# Buffer.net
KiCad netlist of a schematic drawn in Altium Designer
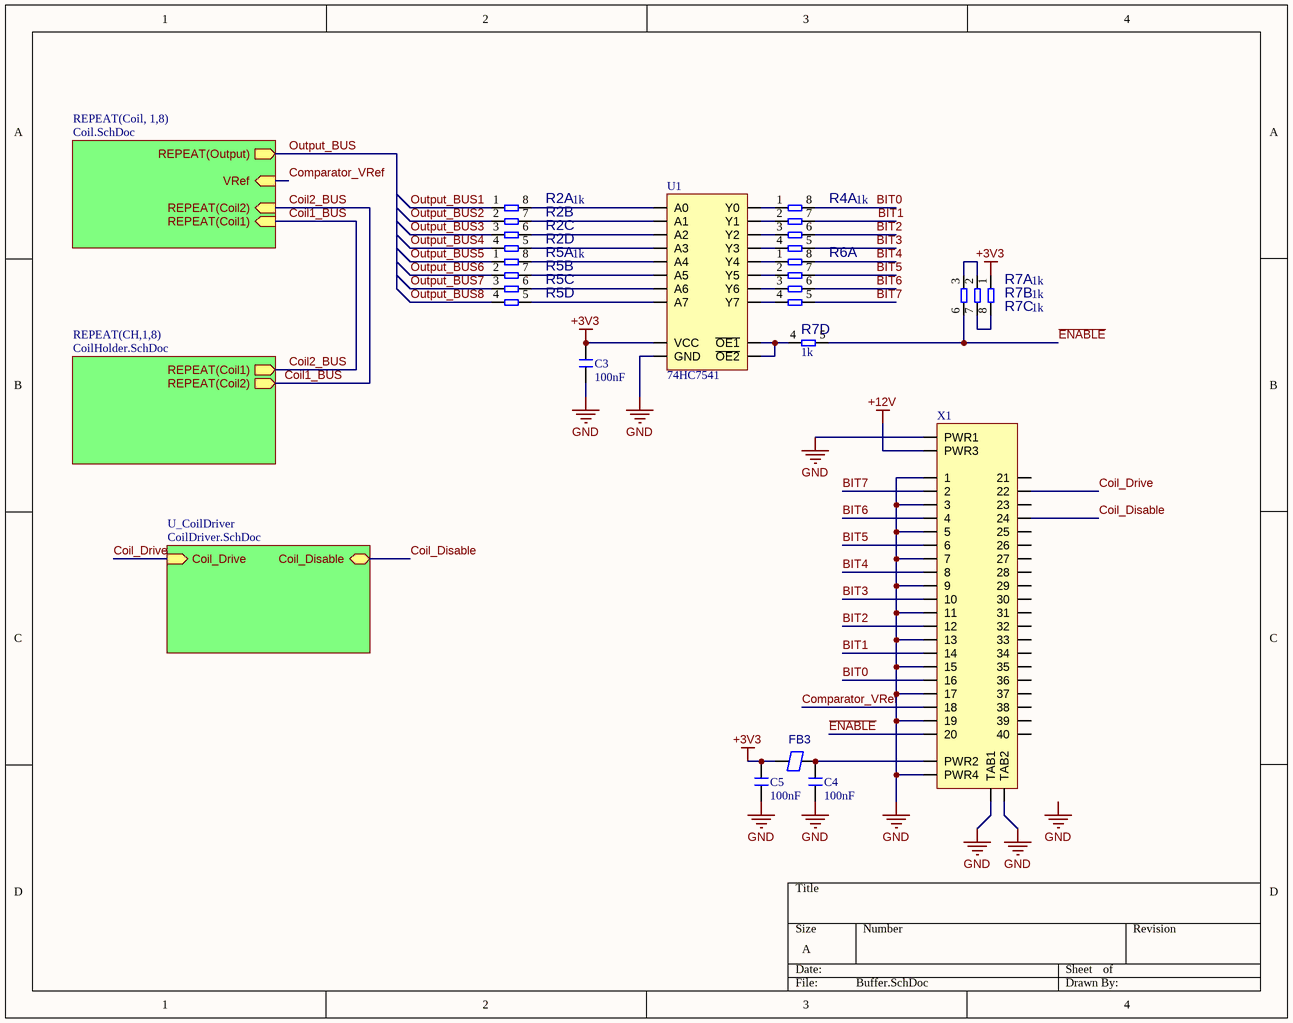
[diagram p0: Buffer.SchDoc]

(export (version "E")
  (design (tool "Eeschema 10.0.6"))
  (components
    (comp (ref "C3")
      (value "100nF")
      (footprint "C0603_N")
      (description "Capacitor MLCC")
      (fields
        (field (name "MANUFACTURER") "Yageo")
        (field (name "MANUFACTURER PART NUMBER") "CC0603KRX7R9BB104")
      )
      (libsource (lib "wes") (part "Capacitor"))
    )
    (comp (ref "C4")
      (value "100nF")
      (footprint "C0603_N")
      (description "Capacitor MLCC")
      (fields
        (field (name "MANUFACTURER") "Yageo")
        (field (name "MANUFACTURER PART NUMBER") "CC0603KRX7R9BB104")
      )
      (libsource (lib "wes") (part "Capacitor"))
    )
    (comp (ref "C5")
      (value "100nF")
      (footprint "C0603_N")
      (description "Capacitor MLCC")
      (fields
        (field (name "MANUFACTURER") "Yageo")
        (field (name "MANUFACTURER PART NUMBER") "CC0603KRX7R9BB104")
      )
      (libsource (lib "wes") (part "Capacitor"))
    )
    (comp (ref "FB3")
      (value "Ferrite Bead")
      (footprint "F0603_N")
      (libsource (lib "wes") (part "Ferrite Bead"))
    )
    (comp (ref "R2")
      (value "Resistor Array - 4P")
      (footprint "YC164")
      (fields (field (name "Comment") "Resistor Array - 4P"))
      (libsource (lib "wes") (part "Resistor Array - 4P"))
    )
    (comp (ref "R4")
      (value "1k")
      (footprint "YC164")
      (fields (field (name "Comment") "Resistor Array - 4P"))
      (libsource (lib "wes") (part "Resistor Array - 4P"))
    )
    (comp (ref "R5")
      (value "Resistor Array - 4P")
      (footprint "YC164")
      (libsource (lib "wes") (part "Resistor Array - 4P"))
    )
    (comp (ref "R6")
      (value "Resistor Array - 4P")
      (footprint "YC164")
      (libsource (lib "wes") (part "Resistor Array - 4P"))
    )
    (comp (ref "R7")
      (value "1k")
      (footprint "YC164")
      (fields (field (name "Comment") "Resistor Array - 4P"))
      (libsource (lib "wes") (part "Resistor Array - 4P"))
    )
    (comp (ref "U1")
      (value "74HC7541")
      (footprint "TSSOP20_N")
      (description "Schmitt Trigger Octal")
      (libsource (lib "wes") (part "74HC7541"))
    )
    (comp (ref "X1")
      (value "FX23 Right Angle Receptacle")
      (footprint "FX23-40S-0.5SH")
      (description "FX23 Right Angle Receptacle 40 Pos")
      (libsource (lib "wes") (part "FX23-40S-0.5SH"))
    )
  )
  (nets
    (net (code "1") (name "+3V3") (class "Default")
      (node (ref "C3") (pin "1") (pintype "passive"))
      (node (ref "C5") (pin "1") (pintype "passive"))
      (node (ref "FB3") (pin "2") (pinfunction "2_2") (pintype "passive"))
      (node (ref "R7") (pin "1") (pinfunction "1_1") (pintype "passive"))
      (node (ref "U1") (pin "20") (pinfunction "VCC_20") (pintype "passive"))
    )
    (net (code "2") (name "+12V") (class "Default")
      (node (ref "X1") (pin "PWR3") (pinfunction "PWR3_PWR3") (pintype "power_in"))
    )
    (net (code "3") (name "/BIT0") (class "Default")
      (node (ref "R4") (pin "8") (pinfunction "8_8") (pintype "passive"))
      (node (ref "X1") (pin "16") (pinfunction "16_16") (pintype "power_in"))
    )
    (net (code "4") (name "/BIT1") (class "Default")
      (node (ref "R4") (pin "7") (pinfunction "7_7") (pintype "passive"))
      (node (ref "X1") (pin "14") (pinfunction "14_14") (pintype "power_in"))
    )
    (net (code "5") (name "/BIT2") (class "Default")
      (node (ref "R4") (pin "6") (pinfunction "6_6") (pintype "passive"))
      (node (ref "X1") (pin "12") (pinfunction "12_12") (pintype "power_in"))
    )
    (net (code "6") (name "/BIT3") (class "Default")
      (node (ref "R4") (pin "5") (pinfunction "5_5") (pintype "passive"))
      (node (ref "X1") (pin "10") (pinfunction "10_10") (pintype "power_in"))
    )
    (net (code "7") (name "/BIT4") (class "Default")
      (node (ref "R6") (pin "8") (pinfunction "8_8") (pintype "passive"))
      (node (ref "X1") (pin "8") (pinfunction "8_8") (pintype "power_in"))
    )
    (net (code "8") (name "/BIT5") (class "Default")
      (node (ref "R6") (pin "7") (pinfunction "7_7") (pintype "passive"))
      (node (ref "X1") (pin "6") (pinfunction "6_6") (pintype "power_in"))
    )
    (net (code "9") (name "/BIT6") (class "Default")
      (node (ref "R6") (pin "6") (pinfunction "6_6") (pintype "passive"))
      (node (ref "X1") (pin "4") (pinfunction "4_4") (pintype "power_in"))
    )
    (net (code "10") (name "/BIT7") (class "Default")
      (node (ref "R6") (pin "5") (pinfunction "5_5") (pintype "passive"))
      (node (ref "X1") (pin "2") (pinfunction "2_2") (pintype "power_in"))
    )
    (net (code "13") (name "/Coil_Disable") (class "Default")
      (node (ref "X1") (pin "24") (pinfunction "24_24") (pintype "power_in"))
    )
    (net (code "14") (name "/Coil_Drive") (class "Default")
      (node (ref "X1") (pin "22") (pinfunction "22_22") (pintype "power_in"))
    )
    (net (code "15") (name "/Comparator_VRef") (class "Default")
      (node (ref "X1") (pin "18") (pinfunction "18_18") (pintype "power_in"))
    )
    (net (code "17") (name "/Output_BUS1") (class "Default")
      (node (ref "R2") (pin "1") (pinfunction "1_1") (pintype "passive"))
    )
    (net (code "18") (name "/Output_BUS2") (class "Default")
      (node (ref "R2") (pin "2") (pinfunction "2_2") (pintype "passive"))
    )
    (net (code "19") (name "/Output_BUS3") (class "Default")
      (node (ref "R2") (pin "3") (pinfunction "3_3") (pintype "passive"))
    )
    (net (code "20") (name "/Output_BUS4") (class "Default")
      (node (ref "R2") (pin "4") (pinfunction "4_4") (pintype "passive"))
    )
    (net (code "21") (name "/Output_BUS5") (class "Default")
      (node (ref "R5") (pin "1") (pinfunction "1_1") (pintype "passive"))
    )
    (net (code "22") (name "/Output_BUS6") (class "Default")
      (node (ref "R5") (pin "2") (pinfunction "2_2") (pintype "passive"))
    )
    (net (code "23") (name "/Output_BUS7") (class "Default")
      (node (ref "R5") (pin "3") (pinfunction "3_3") (pintype "passive"))
    )
    (net (code "24") (name "/Output_BUS8") (class "Default")
      (node (ref "R5") (pin "4") (pinfunction "4_4") (pintype "passive"))
    )
    (net (code "25") (name "/~{ENABLE}") (class "Default")
      (node (ref "R7") (pin "5") (pinfunction "5_5") (pintype "passive"))
      (node (ref "R7") (pin "6") (pinfunction "6_6") (pintype "passive"))
      (node (ref "X1") (pin "20") (pinfunction "20_20") (pintype "power_in"))
    )
    (net (code "26") (name "GND") (class "Default")
      (node (ref "C3") (pin "2") (pintype "passive"))
      (node (ref "C4") (pin "2") (pintype "passive"))
      (node (ref "C5") (pin "2") (pintype "passive"))
      (node (ref "U1") (pin "10") (pinfunction "GND_10") (pintype "passive"))
      (node (ref "X1") (pin "1") (pinfunction "1_1") (pintype "power_in"))
      (node (ref "X1") (pin "11") (pinfunction "11_11") (pintype "power_in"))
      (node (ref "X1") (pin "13") (pinfunction "13_13") (pintype "power_in"))
      (node (ref "X1") (pin "15") (pinfunction "15_15") (pintype "power_in"))
      (node (ref "X1") (pin "17") (pinfunction "17_17") (pintype "power_in"))
      (node (ref "X1") (pin "19") (pinfunction "19_19") (pintype "power_in"))
      (node (ref "X1") (pin "3") (pinfunction "3_3") (pintype "power_in"))
      (node (ref "X1") (pin "5") (pinfunction "5_5") (pintype "power_in"))
      (node (ref "X1") (pin "7") (pinfunction "7_7") (pintype "power_in"))
      (node (ref "X1") (pin "9") (pinfunction "9_9") (pintype "power_in"))
      (node (ref "X1") (pin "PWR1") (pinfunction "PWR1_PWR1") (pintype "power_in"))
      (node (ref "X1") (pin "PWR4") (pinfunction "PWR4_PWR4") (pintype "power_in"))
      (node (ref "X1") (pin "TAB1") (pinfunction "TAB1_TAB1") (pintype "power_in"))
      (node (ref "X1") (pin "TAB2") (pinfunction "TAB2_TAB2") (pintype "power_in"))
    )
    (net (code "27") (name "Net-(C4-Pad1)") (class "Default")
      (node (ref "C4") (pin "1") (pintype "passive"))
      (node (ref "FB3") (pin "1") (pinfunction "1_1") (pintype "passive"))
      (node (ref "X1") (pin "PWR2") (pinfunction "PWR2_PWR2") (pintype "power_in"))
    )
    (net (code "28") (name "Net-(R7-Pad2)") (class "Default")
      (node (ref "R7") (pin "2") (pinfunction "2_2") (pintype "passive"))
      (node (ref "R7") (pin "3") (pinfunction "3_3") (pintype "passive"))
    )
    (net (code "29") (name "Net-(R7-Pad7)") (class "Default")
      (node (ref "R7") (pin "7") (pinfunction "7_7") (pintype "passive"))
      (node (ref "R7") (pin "8") (pinfunction "8_8") (pintype "passive"))
    )
    (net (code "30") (name "Net-(U1-A0)") (class "Default")
      (node (ref "R2") (pin "8") (pinfunction "8_8") (pintype "passive"))
      (node (ref "U1") (pin "2") (pinfunction "A0_2") (pintype "passive"))
    )
    (net (code "31") (name "Net-(U1-A1)") (class "Default")
      (node (ref "R2") (pin "7") (pinfunction "7_7") (pintype "passive"))
      (node (ref "U1") (pin "3") (pinfunction "A1_3") (pintype "passive"))
    )
    (net (code "32") (name "Net-(U1-A2)") (class "Default")
      (node (ref "R2") (pin "6") (pinfunction "6_6") (pintype "passive"))
      (node (ref "U1") (pin "4") (pinfunction "A2_4") (pintype "passive"))
    )
    (net (code "33") (name "Net-(U1-A3)") (class "Default")
      (node (ref "R2") (pin "5") (pinfunction "5_5") (pintype "passive"))
      (node (ref "U1") (pin "5") (pinfunction "A3_5") (pintype "passive"))
    )
    (net (code "34") (name "Net-(U1-A4)") (class "Default")
      (node (ref "R5") (pin "8") (pinfunction "8_8") (pintype "passive"))
      (node (ref "U1") (pin "6") (pinfunction "A4_6") (pintype "passive"))
    )
    (net (code "35") (name "Net-(U1-A5)") (class "Default")
      (node (ref "R5") (pin "7") (pinfunction "7_7") (pintype "passive"))
      (node (ref "U1") (pin "7") (pinfunction "A5_7") (pintype "passive"))
    )
    (net (code "36") (name "Net-(U1-A6)") (class "Default")
      (node (ref "R5") (pin "6") (pinfunction "6_6") (pintype "passive"))
      (node (ref "U1") (pin "8") (pinfunction "A6_8") (pintype "passive"))
    )
    (net (code "37") (name "Net-(U1-A7)") (class "Default")
      (node (ref "R5") (pin "5") (pinfunction "5_5") (pintype "passive"))
      (node (ref "U1") (pin "9") (pinfunction "A7_9") (pintype "passive"))
    )
    (net (code "38") (name "Net-(U1-Y0)") (class "Default")
      (node (ref "R4") (pin "1") (pinfunction "1_1") (pintype "passive"))
      (node (ref "U1") (pin "18") (pinfunction "Y0_18") (pintype "passive"))
    )
    (net (code "39") (name "Net-(U1-Y1)") (class "Default")
      (node (ref "R4") (pin "2") (pinfunction "2_2") (pintype "passive"))
      (node (ref "U1") (pin "17") (pinfunction "Y1_17") (pintype "passive"))
    )
    (net (code "40") (name "Net-(U1-Y2)") (class "Default")
      (node (ref "R4") (pin "3") (pinfunction "3_3") (pintype "passive"))
      (node (ref "U1") (pin "16") (pinfunction "Y2_16") (pintype "passive"))
    )
    (net (code "41") (name "Net-(U1-Y3)") (class "Default")
      (node (ref "R4") (pin "4") (pinfunction "4_4") (pintype "passive"))
      (node (ref "U1") (pin "15") (pinfunction "Y3_15") (pintype "passive"))
    )
    (net (code "42") (name "Net-(U1-Y4)") (class "Default")
      (node (ref "R6") (pin "1") (pinfunction "1_1") (pintype "passive"))
      (node (ref "U1") (pin "14") (pinfunction "Y4_14") (pintype "passive"))
    )
    (net (code "43") (name "Net-(U1-Y5)") (class "Default")
      (node (ref "R6") (pin "2") (pinfunction "2_2") (pintype "passive"))
      (node (ref "U1") (pin "13") (pinfunction "Y5_13") (pintype "passive"))
    )
    (net (code "44") (name "Net-(U1-Y6)") (class "Default")
      (node (ref "R6") (pin "3") (pinfunction "3_3") (pintype "passive"))
      (node (ref "U1") (pin "12") (pinfunction "Y6_12") (pintype "passive"))
    )
    (net (code "45") (name "Net-(U1-Y7)") (class "Default")
      (node (ref "R6") (pin "4") (pinfunction "4_4") (pintype "passive"))
      (node (ref "U1") (pin "11") (pinfunction "Y7_11") (pintype "passive"))
    )
    (net (code "46") (name "Net-(U1-~{OE1})") (class "Default")
      (node (ref "R7") (pin "4") (pinfunction "4_4") (pintype "passive"))
      (node (ref "U1") (pin "1") (pinfunction "~{OE1}_1") (pintype "passive"))
      (node (ref "U1") (pin "19") (pinfunction "~{OE2}_19") (pintype "passive"))
    )
    (net (code "47") (name "unconnected-(X1-Pad21)") (class "Default")
      (node (ref "X1") (pin "21") (pinfunction "21_21") (pintype "power_in"))
    )
    (net (code "48") (name "unconnected-(X1-Pad23)") (class "Default")
      (node (ref "X1") (pin "23") (pinfunction "23_23") (pintype "power_in"))
    )
    (net (code "49") (name "unconnected-(X1-Pad25)") (class "Default")
      (node (ref "X1") (pin "25") (pinfunction "25_25") (pintype "power_in"))
    )
    (net (code "50") (name "unconnected-(X1-Pad26)") (class "Default")
      (node (ref "X1") (pin "26") (pinfunction "26_26") (pintype "power_in"))
    )
    (net (code "51") (name "unconnected-(X1-Pad27)") (class "Default")
      (node (ref "X1") (pin "27") (pinfunction "27_27") (pintype "power_in"))
    )
    (net (code "52") (name "unconnected-(X1-Pad28)") (class "Default")
      (node (ref "X1") (pin "28") (pinfunction "28_28") (pintype "power_in"))
    )
    (net (code "53") (name "unconnected-(X1-Pad29)") (class "Default")
      (node (ref "X1") (pin "29") (pinfunction "29_29") (pintype "power_in"))
    )
    (net (code "54") (name "unconnected-(X1-Pad30)") (class "Default")
      (node (ref "X1") (pin "30") (pinfunction "30_30") (pintype "power_in"))
    )
    (net (code "55") (name "unconnected-(X1-Pad31)") (class "Default")
      (node (ref "X1") (pin "31") (pinfunction "31_31") (pintype "power_in"))
    )
    (net (code "56") (name "unconnected-(X1-Pad32)") (class "Default")
      (node (ref "X1") (pin "32") (pinfunction "32_32") (pintype "power_in"))
    )
    (net (code "57") (name "unconnected-(X1-Pad33)") (class "Default")
      (node (ref "X1") (pin "33") (pinfunction "33_33") (pintype "power_in"))
    )
    (net (code "58") (name "unconnected-(X1-Pad34)") (class "Default")
      (node (ref "X1") (pin "34") (pinfunction "34_34") (pintype "power_in"))
    )
    (net (code "59") (name "unconnected-(X1-Pad35)") (class "Default")
      (node (ref "X1") (pin "35") (pinfunction "35_35") (pintype "power_in"))
    )
    (net (code "60") (name "unconnected-(X1-Pad36)") (class "Default")
      (node (ref "X1") (pin "36") (pinfunction "36_36") (pintype "power_in"))
    )
    (net (code "61") (name "unconnected-(X1-Pad37)") (class "Default")
      (node (ref "X1") (pin "37") (pinfunction "37_37") (pintype "power_in"))
    )
    (net (code "62") (name "unconnected-(X1-Pad38)") (class "Default")
      (node (ref "X1") (pin "38") (pinfunction "38_38") (pintype "power_in"))
    )
    (net (code "63") (name "unconnected-(X1-Pad39)") (class "Default")
      (node (ref "X1") (pin "39") (pinfunction "39_39") (pintype "power_in"))
    )
    (net (code "64") (name "unconnected-(X1-Pad40)") (class "Default")
      (node (ref "X1") (pin "40") (pinfunction "40_40") (pintype "power_in"))
    )
  )
)
